# STBlitter_RevC2.net
KiCad netlist of a schematic drawn in EAGLE
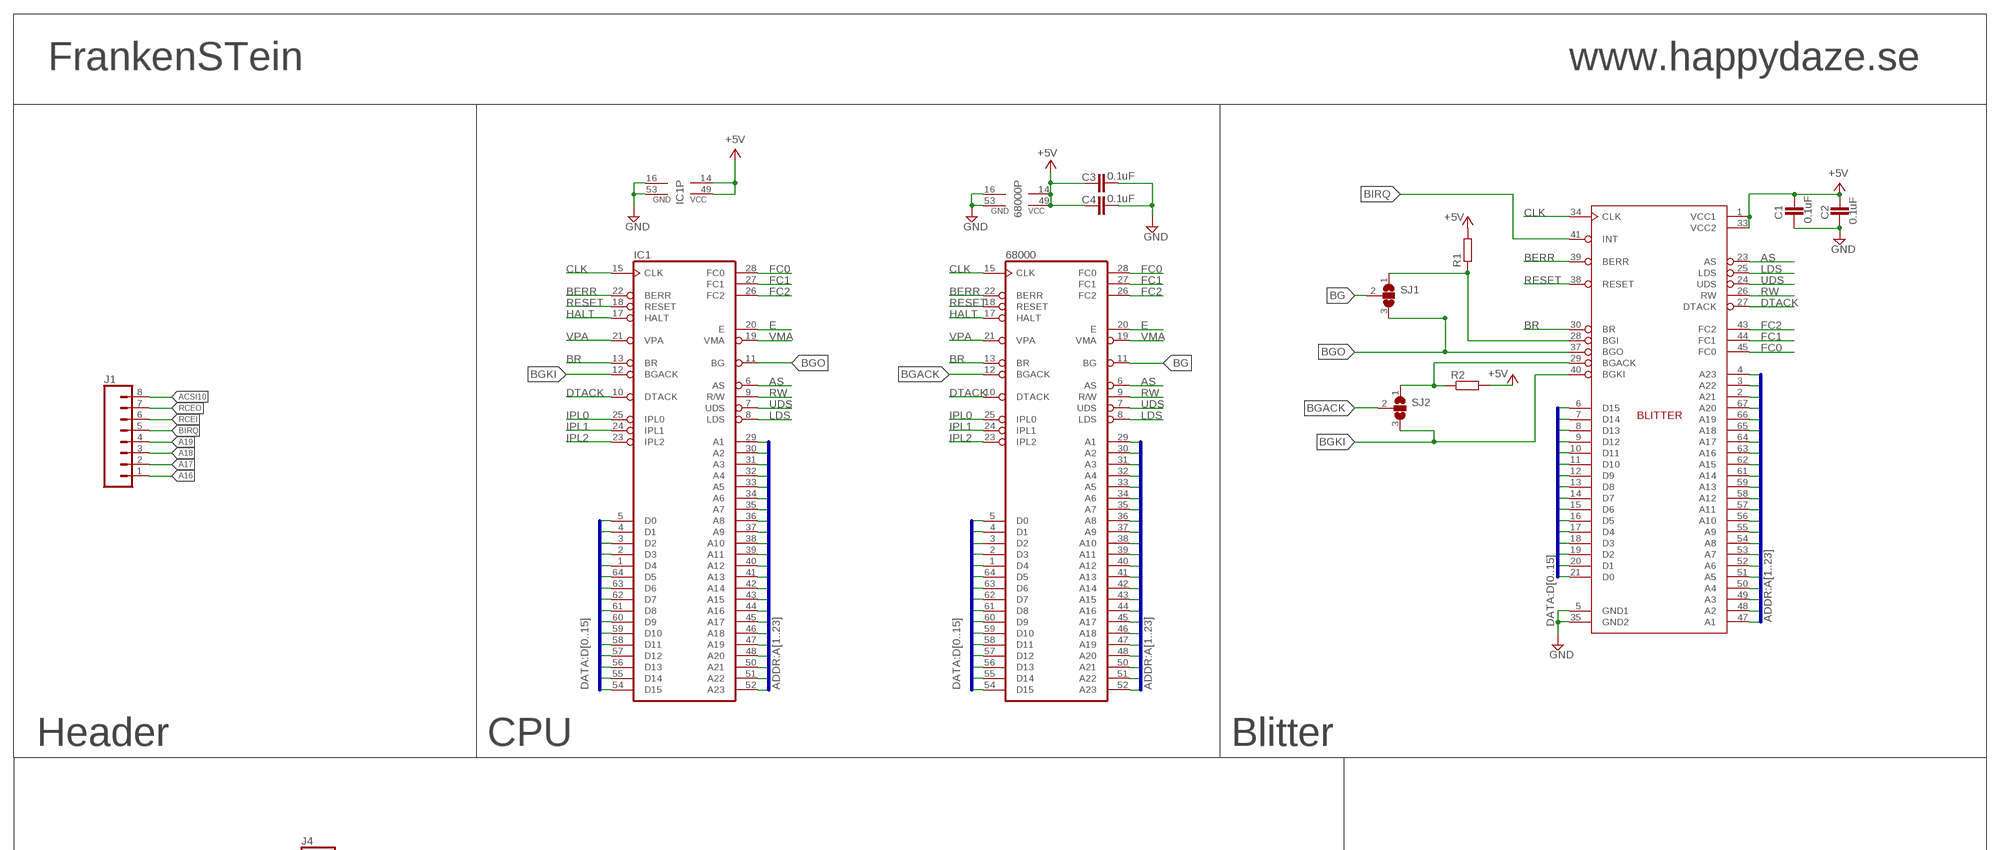
[diagram p0: schematic, sheet 1, part 1 of 2]
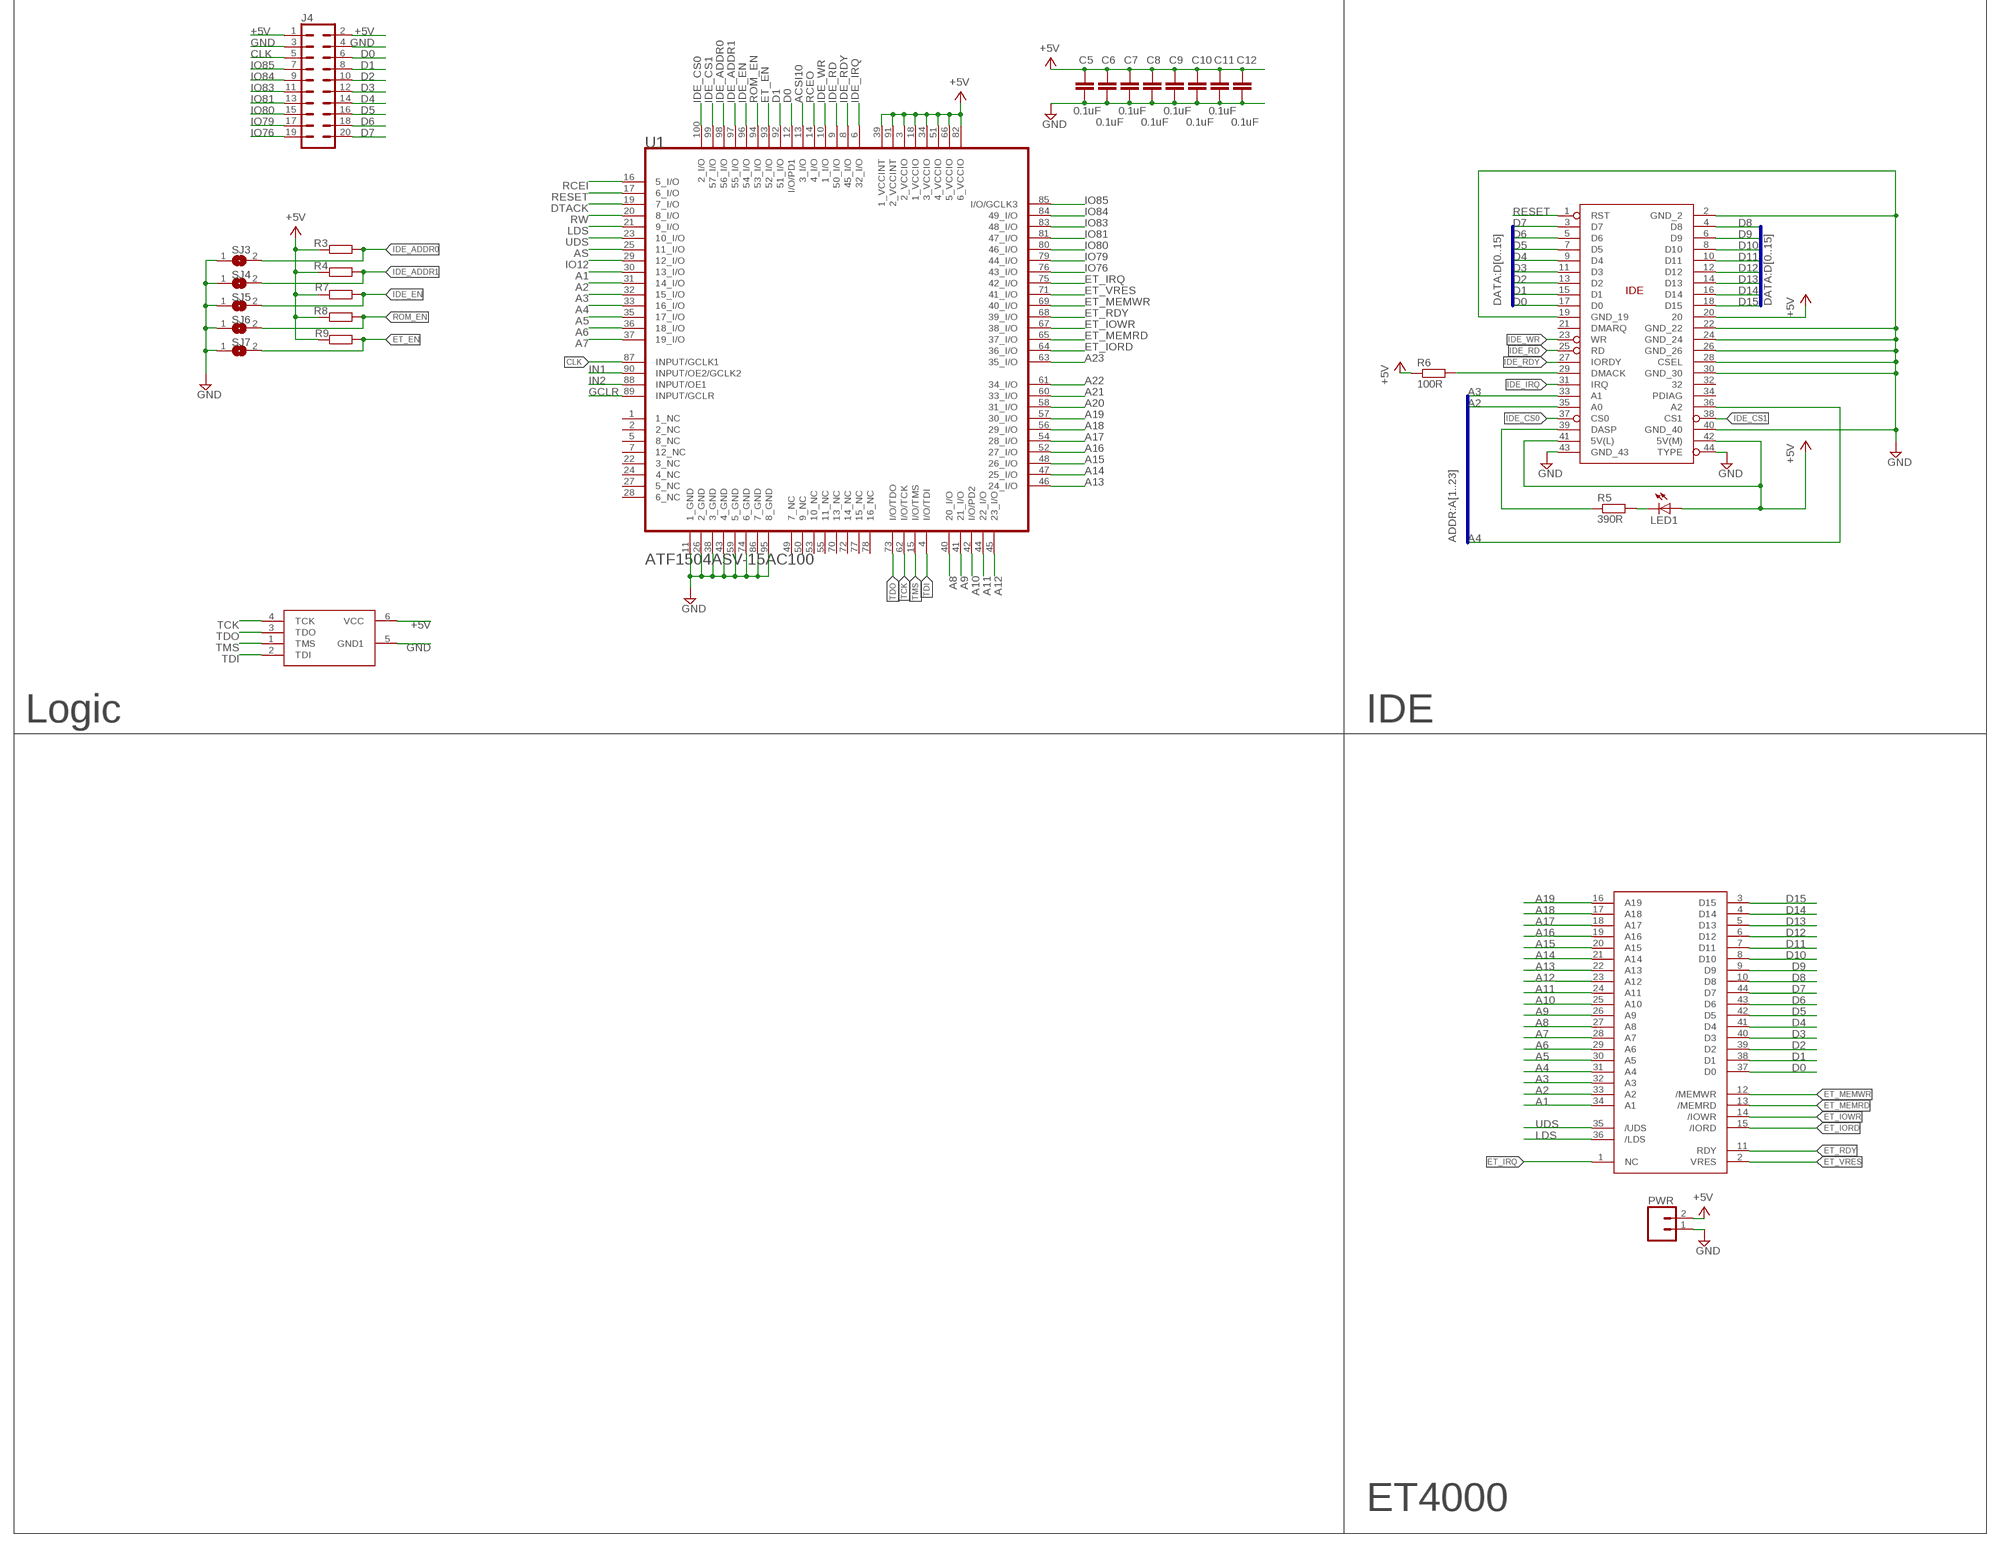
[diagram p1: schematic, sheet 1, part 2 of 2]

(export (version "E")
  (design (tool "Eeschema 10.0.6"))
  (components
    (comp (ref "68000")
      (value "MC68000P")
      (footprint "eagle-import:DIL64")
      (libsource (lib "eagle-import") (part "MC68000P"))
    )
    (comp (ref "BLITTER")
      (value "STBLITTER")
      (footprint "eagle-import:PLCC68-S")
      (libsource (lib "eagle-import") (part "STBLITTER"))
    )
    (comp (ref "C1")
      (value "0.1uF")
      (footprint "eagle-import:C0805")
      (libsource (lib "eagle-import") (part "C-EUC0805"))
    )
    (comp (ref "C2")
      (value "0.1uF")
      (footprint "eagle-import:C0805")
      (libsource (lib "eagle-import") (part "C-EUC0805"))
    )
    (comp (ref "C3")
      (value "0.1uF")
      (footprint "eagle-import:C0805")
      (libsource (lib "eagle-import") (part "C-EUC0805"))
    )
    (comp (ref "C4")
      (value "0.1uF")
      (footprint "eagle-import:C0805")
      (libsource (lib "eagle-import") (part "C-EUC0805"))
    )
    (comp (ref "C5")
      (value "0.1uF")
      (footprint "eagle-import:C0805")
      (libsource (lib "eagle-import") (part "C-EUC0805"))
    )
    (comp (ref "C6")
      (value "0.1uF")
      (footprint "eagle-import:C0805")
      (libsource (lib "eagle-import") (part "C-EUC0805"))
    )
    (comp (ref "C7")
      (value "0.1uF")
      (footprint "eagle-import:C0805")
      (libsource (lib "eagle-import") (part "C-EUC0805"))
    )
    (comp (ref "C8")
      (value "0.1uF")
      (footprint "eagle-import:C0805")
      (libsource (lib "eagle-import") (part "C-EUC0805"))
    )
    (comp (ref "C9")
      (value "0.1uF")
      (footprint "eagle-import:C0805")
      (libsource (lib "eagle-import") (part "C-EUC0805"))
    )
    (comp (ref "C10")
      (value "0.1uF")
      (footprint "eagle-import:C0805")
      (libsource (lib "eagle-import") (part "C-EUC0805"))
    )
    (comp (ref "C11")
      (value "0.1uF")
      (footprint "eagle-import:C0805")
      (libsource (lib "eagle-import") (part "C-EUC0805"))
    )
    (comp (ref "C12")
      (value "0.1uF")
      (footprint "eagle-import:C0805")
      (libsource (lib "eagle-import") (part "C-EUC0805"))
    )
    (comp (ref "CFCARD")
      (value "IDE44_CON")
      (footprint "eagle-import:IDE44_CON")
      (libsource (lib "eagle-import") (part "IDE44_CON"))
    )
    (comp (ref "IC1")
      (value "MC68000P2")
      (footprint "eagle-import:DIL64_SOCKET")
      (libsource (lib "eagle-import") (part "MC68000P2"))
    )
    (comp (ref "J1")
      (value "CONN_08\"")
      (footprint "eagle-import:1X08")
      (libsource (lib "eagle-import") (part "CONN_08{dblquote}"))
    )
    (comp (ref "J4")
      (value "CONN_10X2")
      (footprint "eagle-import:2X10")
      (libsource (lib "eagle-import") (part "CONN_10X2"))
    )
    (comp (ref "JTAG")
      (value "JTAG_ATDH2")
      (footprint "eagle-import:JTAG_ATDH2")
      (libsource (lib "eagle-import") (part "JTAG_ATDH2"))
    )
    (comp (ref "LED1")
      (value "LED3MM")
      (footprint "eagle-import:LED3MM")
      (libsource (lib "eagle-import") (part "LED3MM"))
    )
    (comp (ref "PWR")
      (value "CONN_02")
      (footprint "eagle-import:1X02")
      (libsource (lib "eagle-import") (part "CONN_02"))
    )
    (comp (ref "R1")
      (value "R-EU_R0805")
      (footprint "eagle-import:R0805")
      (libsource (lib "eagle-import") (part "R-EU_R0805"))
    )
    (comp (ref "R2")
      (value "R-EU_R0805")
      (footprint "eagle-import:R0805")
      (libsource (lib "eagle-import") (part "R-EU_R0805"))
    )
    (comp (ref "R3")
      (value "R-EU_R0805")
      (footprint "eagle-import:R0805")
      (libsource (lib "eagle-import") (part "R-EU_R0805"))
    )
    (comp (ref "R4")
      (value "R-EU_R0805")
      (footprint "eagle-import:R0805")
      (libsource (lib "eagle-import") (part "R-EU_R0805"))
    )
    (comp (ref "R5")
      (value "390R")
      (footprint "eagle-import:R0805")
      (libsource (lib "eagle-import") (part "R-EU_R0805"))
    )
    (comp (ref "R6")
      (value "100R")
      (footprint "eagle-import:R0805")
      (libsource (lib "eagle-import") (part "R-EU_R0805"))
    )
    (comp (ref "R7")
      (value "R-EU_R0805")
      (footprint "eagle-import:R0805")
      (libsource (lib "eagle-import") (part "R-EU_R0805"))
    )
    (comp (ref "R8")
      (value "R-EU_R0805")
      (footprint "eagle-import:R0805")
      (libsource (lib "eagle-import") (part "R-EU_R0805"))
    )
    (comp (ref "R9")
      (value "R-EU_R0805")
      (footprint "eagle-import:R0805")
      (libsource (lib "eagle-import") (part "R-EU_R0805"))
    )
    (comp (ref "SJ1")
      (value "SJ2W")
      (footprint "eagle-import:SJ_2")
      (libsource (lib "eagle-import") (part "SJ2W"))
    )
    (comp (ref "SJ2")
      (value "SJ2W")
      (footprint "eagle-import:SJ_2")
      (libsource (lib "eagle-import") (part "SJ2W"))
    )
    (comp (ref "SJ3") (value "SJ") (footprint "eagle-import:SJ") (libsource (lib "eagle-import") (part "SJ")))
    (comp (ref "SJ4") (value "SJ") (footprint "eagle-import:SJ") (libsource (lib "eagle-import") (part "SJ")))
    (comp (ref "SJ5") (value "SJ") (footprint "eagle-import:SJ") (libsource (lib "eagle-import") (part "SJ")))
    (comp (ref "SJ6") (value "SJ") (footprint "eagle-import:SJ") (libsource (lib "eagle-import") (part "SJ")))
    (comp (ref "SJ7") (value "SJ") (footprint "eagle-import:SJ") (libsource (lib "eagle-import") (part "SJ")))
    (comp (ref "STGA")
      (value "STGA")
      (footprint "eagle-import:STGACON")
      (libsource (lib "eagle-import") (part "STGA"))
    )
    (comp (ref "U1")
      (value "ATF1504_SMD100MICROCHIP_-_ATMEL_ATF1504ASV-15AC100_0_1")
      (footprint "eagle-import:MICROCHIP_-_ATMEL_ATF1504ASV-15AC100_1")
      (fields (field (name "MF") "Microchip / Atmel") (field (name "MPN") "ATF1504ASV-15AC100"))
      (libsource (lib "eagle-import") (part "ATF1504_SMD100MICROCHIP_-_ATMEL_ATF1504ASV-15AC100_0_1"))
    )
  )
  (nets
    (net (code "40") (name "+5V") (class "Default")
      (node (ref "68000") (pin "14") (pinfunction "VCC_14") (pintype "power_in"))
      (node (ref "68000") (pin "49") (pinfunction "VCC_49") (pintype "power_in"))
      (node (ref "BLITTER") (pin "1") (pinfunction "VCC1_1") (pintype "power_in"))
      (node (ref "BLITTER") (pin "33") (pinfunction "VCC2_33") (pintype "power_in"))
      (node (ref "C1") (pin "1") (pinfunction "1_1") (pintype "passive"))
      (node (ref "C10") (pin "2") (pinfunction "2_2") (pintype "passive"))
      (node (ref "C11") (pin "2") (pinfunction "2_2") (pintype "passive"))
      (node (ref "C12") (pin "2") (pinfunction "2_2") (pintype "passive"))
      (node (ref "C2") (pin "1") (pinfunction "1_1") (pintype "passive"))
      (node (ref "C3") (pin "1") (pinfunction "1_1") (pintype "passive"))
      (node (ref "C4") (pin "1") (pinfunction "1_1") (pintype "passive"))
      (node (ref "C5") (pin "2") (pinfunction "2_2") (pintype "passive"))
      (node (ref "C6") (pin "2") (pinfunction "2_2") (pintype "passive"))
      (node (ref "C7") (pin "2") (pinfunction "2_2") (pintype "passive"))
      (node (ref "C8") (pin "2") (pinfunction "2_2") (pintype "passive"))
      (node (ref "C9") (pin "2") (pinfunction "2_2") (pintype "passive"))
      (node (ref "CFCARD") (pin "20") (pinfunction "20_20") (pintype "bidirectional"))
      (node (ref "CFCARD") (pin "41") (pinfunction "5V(L)_41") (pintype "bidirectional"))
      (node (ref "CFCARD") (pin "42") (pinfunction "5V(M)_42") (pintype "bidirectional"))
      (node (ref "IC1") (pin "14") (pinfunction "VCC_14") (pintype "power_in"))
      (node (ref "IC1") (pin "49") (pinfunction "VCC_49") (pintype "power_in"))
      (node (ref "J4") (pin "1") (pinfunction "1_1") (pintype "passive"))
      (node (ref "J4") (pin "2") (pinfunction "2_2") (pintype "passive"))
      (node (ref "JTAG") (pin "6") (pinfunction "VCC_6") (pintype "bidirectional"))
      (node (ref "LED1") (pin "A") (pinfunction "A_A") (pintype "passive"))
      (node (ref "PWR") (pin "2") (pinfunction "2_2") (pintype "passive"))
      (node (ref "R1") (pin "2") (pinfunction "2_2") (pintype "passive"))
      (node (ref "R2") (pin "2") (pinfunction "2_2") (pintype "passive"))
      (node (ref "R3") (pin "1") (pinfunction "1_1") (pintype "passive"))
      (node (ref "R4") (pin "1") (pinfunction "1_1") (pintype "passive"))
      (node (ref "R6") (pin "1") (pinfunction "1_1") (pintype "passive"))
      (node (ref "R7") (pin "1") (pinfunction "1_1") (pintype "passive"))
      (node (ref "R8") (pin "1") (pinfunction "1_1") (pintype "passive"))
      (node (ref "R9") (pin "1") (pinfunction "1_1") (pintype "passive"))
      (node (ref "U1") (pin "18") (pinfunction "1_VCCIO_18") (pintype "power_in"))
      (node (ref "U1") (pin "3") (pinfunction "2_VCCIO_3") (pintype "power_in"))
      (node (ref "U1") (pin "34") (pinfunction "3_VCCIO_34") (pintype "power_in"))
      (node (ref "U1") (pin "39") (pinfunction "1_VCCINT_39") (pintype "power_in"))
      (node (ref "U1") (pin "51") (pinfunction "4_VCCIO_51") (pintype "power_in"))
      (node (ref "U1") (pin "66") (pinfunction "5_VCCIO_66") (pintype "power_in"))
      (node (ref "U1") (pin "82") (pinfunction "6_VCCIO_82") (pintype "power_in"))
      (node (ref "U1") (pin "91") (pinfunction "2_VCCINT_91") (pintype "power_in"))
    )
    (net (code "41") (name "/A1") (class "Default")
      (node (ref "68000") (pin "29") (pinfunction "A1_29") (pintype "output"))
      (node (ref "BLITTER") (pin "47") (pinfunction "A1_47") (pintype "bidirectional"))
      (node (ref "IC1") (pin "29") (pinfunction "A1_29") (pintype "output"))
      (node (ref "STGA") (pin "34") (pinfunction "A1_34") (pintype "bidirectional"))
      (node (ref "U1") (pin "30") (pinfunction "13_I/O_30") (pintype "bidirectional"))
    )
    (net (code "42") (name "/A2") (class "Default")
      (node (ref "68000") (pin "30") (pinfunction "A2_30") (pintype "output"))
      (node (ref "BLITTER") (pin "48") (pinfunction "A2_48") (pintype "bidirectional"))
      (node (ref "CFCARD") (pin "35") (pinfunction "A0_35") (pintype "bidirectional"))
      (node (ref "IC1") (pin "30") (pinfunction "A2_30") (pintype "output"))
      (node (ref "STGA") (pin "33") (pinfunction "A2_33") (pintype "bidirectional"))
      (node (ref "U1") (pin "31") (pinfunction "14_I/O_31") (pintype "bidirectional"))
    )
    (net (code "43") (name "/A3") (class "Default")
      (node (ref "68000") (pin "31") (pinfunction "A3_31") (pintype "output"))
      (node (ref "BLITTER") (pin "49") (pinfunction "A3_49") (pintype "bidirectional"))
      (node (ref "CFCARD") (pin "33") (pinfunction "A1_33") (pintype "bidirectional"))
      (node (ref "IC1") (pin "31") (pinfunction "A3_31") (pintype "output"))
      (node (ref "STGA") (pin "32") (pinfunction "A3_32") (pintype "bidirectional"))
      (node (ref "U1") (pin "32") (pinfunction "15_I/O_32") (pintype "bidirectional"))
    )
    (net (code "44") (name "/A4") (class "Default")
      (node (ref "68000") (pin "32") (pinfunction "A4_32") (pintype "output"))
      (node (ref "BLITTER") (pin "50") (pinfunction "A4_50") (pintype "bidirectional"))
      (node (ref "CFCARD") (pin "36") (pinfunction "A2_36") (pintype "bidirectional"))
      (node (ref "IC1") (pin "32") (pinfunction "A4_32") (pintype "output"))
      (node (ref "STGA") (pin "31") (pinfunction "A4_31") (pintype "bidirectional"))
      (node (ref "U1") (pin "33") (pinfunction "16_I/O_33") (pintype "bidirectional"))
    )
    (net (code "45") (name "/A5") (class "Default")
      (node (ref "68000") (pin "33") (pinfunction "A5_33") (pintype "output"))
      (node (ref "BLITTER") (pin "51") (pinfunction "A5_51") (pintype "bidirectional"))
      (node (ref "IC1") (pin "33") (pinfunction "A5_33") (pintype "output"))
      (node (ref "STGA") (pin "30") (pinfunction "A5_30") (pintype "bidirectional"))
      (node (ref "U1") (pin "35") (pinfunction "17_I/O_35") (pintype "bidirectional"))
    )
    (net (code "46") (name "/A6") (class "Default")
      (node (ref "68000") (pin "34") (pinfunction "A6_34") (pintype "output"))
      (node (ref "BLITTER") (pin "52") (pinfunction "A6_52") (pintype "bidirectional"))
      (node (ref "IC1") (pin "34") (pinfunction "A6_34") (pintype "output"))
      (node (ref "STGA") (pin "29") (pinfunction "A6_29") (pintype "bidirectional"))
      (node (ref "U1") (pin "36") (pinfunction "18_I/O_36") (pintype "bidirectional"))
    )
    (net (code "47") (name "/A7") (class "Default")
      (node (ref "68000") (pin "35") (pinfunction "A7_35") (pintype "output"))
      (node (ref "BLITTER") (pin "53") (pinfunction "A7_53") (pintype "bidirectional"))
      (node (ref "IC1") (pin "35") (pinfunction "A7_35") (pintype "output"))
      (node (ref "STGA") (pin "28") (pinfunction "A7_28") (pintype "bidirectional"))
      (node (ref "U1") (pin "37") (pinfunction "19_I/O_37") (pintype "bidirectional"))
    )
    (net (code "48") (name "/A8") (class "Default")
      (node (ref "68000") (pin "36") (pinfunction "A8_36") (pintype "output"))
      (node (ref "BLITTER") (pin "54") (pinfunction "A8_54") (pintype "bidirectional"))
      (node (ref "IC1") (pin "36") (pinfunction "A8_36") (pintype "output"))
      (node (ref "STGA") (pin "27") (pinfunction "A8_27") (pintype "bidirectional"))
      (node (ref "U1") (pin "40") (pinfunction "20_I/O_40") (pintype "bidirectional"))
    )
    (net (code "49") (name "/A9") (class "Default")
      (node (ref "68000") (pin "37") (pinfunction "A9_37") (pintype "output"))
      (node (ref "BLITTER") (pin "55") (pinfunction "A9_55") (pintype "bidirectional"))
      (node (ref "IC1") (pin "37") (pinfunction "A9_37") (pintype "output"))
      (node (ref "STGA") (pin "26") (pinfunction "A9_26") (pintype "bidirectional"))
      (node (ref "U1") (pin "41") (pinfunction "21_I/O_41") (pintype "bidirectional"))
    )
    (net (code "50") (name "/A10") (class "Default")
      (node (ref "68000") (pin "38") (pinfunction "A10_38") (pintype "output"))
      (node (ref "BLITTER") (pin "56") (pinfunction "A10_56") (pintype "bidirectional"))
      (node (ref "IC1") (pin "38") (pinfunction "A10_38") (pintype "output"))
      (node (ref "STGA") (pin "25") (pinfunction "A10_25") (pintype "bidirectional"))
      (node (ref "U1") (pin "42") (pinfunction "I/O/PD2_42") (pintype "bidirectional"))
    )
    (net (code "51") (name "/A11") (class "Default")
      (node (ref "68000") (pin "39") (pinfunction "A11_39") (pintype "output"))
      (node (ref "BLITTER") (pin "57") (pinfunction "A11_57") (pintype "bidirectional"))
      (node (ref "IC1") (pin "39") (pinfunction "A11_39") (pintype "output"))
      (node (ref "STGA") (pin "24") (pinfunction "A11_24") (pintype "bidirectional"))
      (node (ref "U1") (pin "44") (pinfunction "22_I/O_44") (pintype "bidirectional"))
    )
    (net (code "52") (name "/A12") (class "Default")
      (node (ref "68000") (pin "40") (pinfunction "A12_40") (pintype "output"))
      (node (ref "BLITTER") (pin "58") (pinfunction "A12_58") (pintype "bidirectional"))
      (node (ref "IC1") (pin "40") (pinfunction "A12_40") (pintype "output"))
      (node (ref "STGA") (pin "23") (pinfunction "A12_23") (pintype "bidirectional"))
      (node (ref "U1") (pin "45") (pinfunction "23_I/O_45") (pintype "bidirectional"))
    )
    (net (code "53") (name "/A13") (class "Default")
      (node (ref "68000") (pin "41") (pinfunction "A13_41") (pintype "output"))
      (node (ref "BLITTER") (pin "59") (pinfunction "A13_59") (pintype "bidirectional"))
      (node (ref "IC1") (pin "41") (pinfunction "A13_41") (pintype "output"))
      (node (ref "STGA") (pin "22") (pinfunction "A13_22") (pintype "bidirectional"))
      (node (ref "U1") (pin "46") (pinfunction "24_I/O_46") (pintype "bidirectional"))
    )
    (net (code "54") (name "/A14") (class "Default")
      (node (ref "68000") (pin "42") (pinfunction "A14_42") (pintype "output"))
      (node (ref "BLITTER") (pin "61") (pinfunction "A14_61") (pintype "bidirectional"))
      (node (ref "IC1") (pin "42") (pinfunction "A14_42") (pintype "output"))
      (node (ref "STGA") (pin "21") (pinfunction "A14_21") (pintype "bidirectional"))
      (node (ref "U1") (pin "47") (pinfunction "25_I/O_47") (pintype "bidirectional"))
    )
    (net (code "55") (name "/A15") (class "Default")
      (node (ref "68000") (pin "43") (pinfunction "A15_43") (pintype "output"))
      (node (ref "BLITTER") (pin "62") (pinfunction "A15_62") (pintype "bidirectional"))
      (node (ref "IC1") (pin "43") (pinfunction "A15_43") (pintype "output"))
      (node (ref "STGA") (pin "20") (pinfunction "A15_20") (pintype "bidirectional"))
      (node (ref "U1") (pin "48") (pinfunction "26_I/O_48") (pintype "bidirectional"))
    )
    (net (code "56") (name "/A20") (class "Default")
      (node (ref "68000") (pin "48") (pinfunction "A20_48") (pintype "output"))
      (node (ref "BLITTER") (pin "67") (pinfunction "A20_67") (pintype "bidirectional"))
      (node (ref "IC1") (pin "48") (pinfunction "A20_48") (pintype "output"))
      (node (ref "U1") (pin "58") (pinfunction "31_I/O_58") (pintype "bidirectional"))
    )
    (net (code "57") (name "/A21") (class "Default")
      (node (ref "68000") (pin "50") (pinfunction "A21_50") (pintype "output"))
      (node (ref "BLITTER") (pin "2") (pinfunction "A21_2") (pintype "bidirectional"))
      (node (ref "IC1") (pin "50") (pinfunction "A21_50") (pintype "output"))
      (node (ref "U1") (pin "60") (pinfunction "33_I/O_60") (pintype "bidirectional"))
    )
    (net (code "58") (name "/A22") (class "Default")
      (node (ref "68000") (pin "51") (pinfunction "A22_51") (pintype "output"))
      (node (ref "BLITTER") (pin "3") (pinfunction "A22_3") (pintype "bidirectional"))
      (node (ref "IC1") (pin "51") (pinfunction "A22_51") (pintype "output"))
      (node (ref "U1") (pin "61") (pinfunction "34_I/O_61") (pintype "bidirectional"))
    )
    (net (code "59") (name "/A23") (class "Default")
      (node (ref "68000") (pin "52") (pinfunction "A23_52") (pintype "output"))
      (node (ref "BLITTER") (pin "4") (pinfunction "A23_4") (pintype "bidirectional"))
      (node (ref "IC1") (pin "52") (pinfunction "A23_52") (pintype "output"))
      (node (ref "U1") (pin "63") (pinfunction "35_I/O_63") (pintype "bidirectional"))
    )
    (net (code "61") (name "/AS") (class "Default")
      (node (ref "68000") (pin "6") (pinfunction "AS_6") (pintype "output"))
      (node (ref "BLITTER") (pin "23") (pinfunction "AS_23") (pintype "bidirectional"))
      (node (ref "IC1") (pin "6") (pinfunction "AS_6") (pintype "output"))
      (node (ref "U1") (pin "25") (pinfunction "11_I/O_25") (pintype "bidirectional"))
    )
    (net (code "62") (name "/BERR") (class "Default")
      (node (ref "68000") (pin "22") (pinfunction "BERR_22") (pintype "input"))
      (node (ref "BLITTER") (pin "39") (pinfunction "BERR_39") (pintype "bidirectional"))
      (node (ref "IC1") (pin "22") (pinfunction "BERR_22") (pintype "input"))
    )
    (net (code "63") (name "/BR") (class "Default")
      (node (ref "68000") (pin "13") (pinfunction "BR_13") (pintype "input"))
      (node (ref "BLITTER") (pin "30") (pinfunction "BR_30") (pintype "bidirectional"))
      (node (ref "IC1") (pin "13") (pinfunction "BR_13") (pintype "input"))
    )
    (net (code "64") (name "/D0") (class "Default")
      (node (ref "68000") (pin "5") (pinfunction "D0_5") (pintype "bidirectional"))
      (node (ref "BLITTER") (pin "21") (pinfunction "D0_21") (pintype "bidirectional"))
      (node (ref "CFCARD") (pin "17") (pinfunction "D0_17") (pintype "bidirectional"))
      (node (ref "IC1") (pin "5") (pinfunction "D0_5") (pintype "bidirectional"))
      (node (ref "J4") (pin "6") (pinfunction "6_6") (pintype "passive"))
      (node (ref "STGA") (pin "37") (pinfunction "D0_37") (pintype "bidirectional"))
      (node (ref "U1") (pin "12") (pinfunction "I/O/PD1_12") (pintype "bidirectional"))
    )
    (net (code "65") (name "/D1") (class "Default")
      (node (ref "68000") (pin "4") (pinfunction "D1_4") (pintype "bidirectional"))
      (node (ref "BLITTER") (pin "20") (pinfunction "D1_20") (pintype "bidirectional"))
      (node (ref "CFCARD") (pin "15") (pinfunction "D1_15") (pintype "bidirectional"))
      (node (ref "IC1") (pin "4") (pinfunction "D1_4") (pintype "bidirectional"))
      (node (ref "J4") (pin "8") (pinfunction "8_8") (pintype "passive"))
      (node (ref "STGA") (pin "38") (pinfunction "D1_38") (pintype "bidirectional"))
      (node (ref "U1") (pin "92") (pinfunction "51_I/O_92") (pintype "bidirectional"))
    )
    (net (code "66") (name "/D2") (class "Default")
      (node (ref "68000") (pin "3") (pinfunction "D2_3") (pintype "bidirectional"))
      (node (ref "BLITTER") (pin "19") (pinfunction "D2_19") (pintype "bidirectional"))
      (node (ref "CFCARD") (pin "13") (pinfunction "D2_13") (pintype "bidirectional"))
      (node (ref "IC1") (pin "3") (pinfunction "D2_3") (pintype "bidirectional"))
      (node (ref "J4") (pin "10") (pinfunction "10_10") (pintype "passive"))
      (node (ref "STGA") (pin "39") (pinfunction "D2_39") (pintype "bidirectional"))
    )
    (net (code "67") (name "/D3") (class "Default")
      (node (ref "68000") (pin "2") (pinfunction "D3_2") (pintype "bidirectional"))
      (node (ref "BLITTER") (pin "18") (pinfunction "D3_18") (pintype "bidirectional"))
      (node (ref "CFCARD") (pin "11") (pinfunction "D3_11") (pintype "bidirectional"))
      (node (ref "IC1") (pin "2") (pinfunction "D3_2") (pintype "bidirectional"))
      (node (ref "J4") (pin "12") (pinfunction "12_12") (pintype "passive"))
      (node (ref "STGA") (pin "40") (pinfunction "D3_40") (pintype "bidirectional"))
    )
    (net (code "68") (name "/D4") (class "Default")
      (node (ref "68000") (pin "1") (pinfunction "D4_1") (pintype "bidirectional"))
      (node (ref "BLITTER") (pin "17") (pinfunction "D4_17") (pintype "bidirectional"))
      (node (ref "CFCARD") (pin "9") (pinfunction "D4_9") (pintype "bidirectional"))
      (node (ref "IC1") (pin "1") (pinfunction "D4_1") (pintype "bidirectional"))
      (node (ref "J4") (pin "14") (pinfunction "14_14") (pintype "passive"))
      (node (ref "STGA") (pin "41") (pinfunction "D4_41") (pintype "bidirectional"))
    )
    (net (code "69") (name "/D5") (class "Default")
      (node (ref "68000") (pin "64") (pinfunction "D5_64") (pintype "bidirectional"))
      (node (ref "BLITTER") (pin "16") (pinfunction "D5_16") (pintype "bidirectional"))
      (node (ref "CFCARD") (pin "7") (pinfunction "D5_7") (pintype "bidirectional"))
      (node (ref "IC1") (pin "64") (pinfunction "D5_64") (pintype "bidirectional"))
      (node (ref "J4") (pin "16") (pinfunction "16_16") (pintype "passive"))
      (node (ref "STGA") (pin "42") (pinfunction "D5_42") (pintype "bidirectional"))
    )
    (net (code "70") (name "/D6") (class "Default")
      (node (ref "68000") (pin "63") (pinfunction "D6_63") (pintype "bidirectional"))
      (node (ref "BLITTER") (pin "15") (pinfunction "D6_15") (pintype "bidirectional"))
      (node (ref "CFCARD") (pin "5") (pinfunction "D6_5") (pintype "bidirectional"))
      (node (ref "IC1") (pin "63") (pinfunction "D6_63") (pintype "bidirectional"))
      (node (ref "J4") (pin "18") (pinfunction "18_18") (pintype "passive"))
      (node (ref "STGA") (pin "43") (pinfunction "D6_43") (pintype "bidirectional"))
    )
    (net (code "71") (name "/D7") (class "Default")
      (node (ref "68000") (pin "62") (pinfunction "D7_62") (pintype "bidirectional"))
      (node (ref "BLITTER") (pin "14") (pinfunction "D7_14") (pintype "bidirectional"))
      (node (ref "CFCARD") (pin "3") (pinfunction "D7_3") (pintype "bidirectional"))
      (node (ref "IC1") (pin "62") (pinfunction "D7_62") (pintype "bidirectional"))
      (node (ref "J4") (pin "20") (pinfunction "20_20") (pintype "passive"))
      (node (ref "STGA") (pin "44") (pinfunction "D7_44") (pintype "bidirectional"))
    )
    (net (code "72") (name "/D8") (class "Default")
      (node (ref "68000") (pin "61") (pinfunction "D8_61") (pintype "bidirectional"))
      (node (ref "BLITTER") (pin "13") (pinfunction "D8_13") (pintype "bidirectional"))
      (node (ref "CFCARD") (pin "4") (pinfunction "D8_4") (pintype "bidirectional"))
      (node (ref "IC1") (pin "61") (pinfunction "D8_61") (pintype "bidirectional"))
      (node (ref "STGA") (pin "10") (pinfunction "D8_10") (pintype "bidirectional"))
    )
    (net (code "73") (name "/D9") (class "Default")
      (node (ref "68000") (pin "60") (pinfunction "D9_60") (pintype "bidirectional"))
      (node (ref "BLITTER") (pin "12") (pinfunction "D9_12") (pintype "bidirectional"))
      (node (ref "CFCARD") (pin "6") (pinfunction "D9_6") (pintype "bidirectional"))
      (node (ref "IC1") (pin "60") (pinfunction "D9_60") (pintype "bidirectional"))
      (node (ref "STGA") (pin "9") (pinfunction "D9_9") (pintype "bidirectional"))
    )
    (net (code "74") (name "/D10") (class "Default")
      (node (ref "68000") (pin "59") (pinfunction "D10_59") (pintype "bidirectional"))
      (node (ref "BLITTER") (pin "11") (pinfunction "D10_11") (pintype "bidirectional"))
      (node (ref "CFCARD") (pin "8") (pinfunction "D10_8") (pintype "bidirectional"))
      (node (ref "IC1") (pin "59") (pinfunction "D10_59") (pintype "bidirectional"))
      (node (ref "STGA") (pin "8") (pinfunction "D10_8") (pintype "bidirectional"))
    )
    (net (code "75") (name "/D11") (class "Default")
      (node (ref "68000") (pin "58") (pinfunction "D11_58") (pintype "bidirectional"))
      (node (ref "BLITTER") (pin "10") (pinfunction "D11_10") (pintype "bidirectional"))
      (node (ref "CFCARD") (pin "10") (pinfunction "D11_10") (pintype "bidirectional"))
      (node (ref "IC1") (pin "58") (pinfunction "D11_58") (pintype "bidirectional"))
      (node (ref "STGA") (pin "7") (pinfunction "D11_7") (pintype "bidirectional"))
    )
    (net (code "76") (name "/D12") (class "Default")
      (node (ref "68000") (pin "57") (pinfunction "D12_57") (pintype "bidirectional"))
      (node (ref "BLITTER") (pin "9") (pinfunction "D12_9") (pintype "bidirectional"))
      (node (ref "CFCARD") (pin "12") (pinfunction "D12_12") (pintype "bidirectional"))
      (node (ref "IC1") (pin "57") (pinfunction "D12_57") (pintype "bidirectional"))
      (node (ref "STGA") (pin "6") (pinfunction "D12_6") (pintype "bidirectional"))
    )
    (net (code "77") (name "/D13") (class "Default")
      (node (ref "68000") (pin "56") (pinfunction "D13_56") (pintype "bidirectional"))
      (node (ref "BLITTER") (pin "8") (pinfunction "D13_8") (pintype "bidirectional"))
      (node (ref "CFCARD") (pin "14") (pinfunction "D13_14") (pintype "bidirectional"))
      (node (ref "IC1") (pin "56") (pinfunction "D13_56") (pintype "bidirectional"))
      (node (ref "STGA") (pin "5") (pinfunction "D13_5") (pintype "bidirectional"))
    )
    (net (code "78") (name "/D14") (class "Default")
      (node (ref "68000") (pin "55") (pinfunction "D14_55") (pintype "bidirectional"))
      (node (ref "BLITTER") (pin "7") (pinfunction "D14_7") (pintype "bidirectional"))
      (node (ref "CFCARD") (pin "16") (pinfunction "D14_16") (pintype "bidirectional"))
      (node (ref "IC1") (pin "55") (pinfunction "D14_55") (pintype "bidirectional"))
      (node (ref "STGA") (pin "4") (pinfunction "D14_4") (pintype "bidirectional"))
    )
    (net (code "79") (name "/D15") (class "Default")
      (node (ref "68000") (pin "54") (pinfunction "D15_54") (pintype "bidirectional"))
      (node (ref "BLITTER") (pin "6") (pinfunction "D15_6") (pintype "bidirectional"))
      (node (ref "CFCARD") (pin "18") (pinfunction "D15_18") (pintype "bidirectional"))
      (node (ref "IC1") (pin "54") (pinfunction "D15_54") (pintype "bidirectional"))
      (node (ref "STGA") (pin "3") (pinfunction "D15_3") (pintype "bidirectional"))
    )
    (net (code "81") (name "/DTACK") (class "Default")
      (node (ref "68000") (pin "10") (pinfunction "DTACK_10") (pintype "input"))
      (node (ref "BLITTER") (pin "27") (pinfunction "DTACK_27") (pintype "bidirectional"))
      (node (ref "IC1") (pin "10") (pinfunction "DTACK_10") (pintype "input"))
      (node (ref "U1") (pin "19") (pinfunction "7_I/O_19") (pintype "bidirectional"))
    )
    (net (code "82") (name "/E") (class "Default")
      (node (ref "68000") (pin "20") (pinfunction "E_20") (pintype "output"))
      (node (ref "IC1") (pin "20") (pinfunction "E_20") (pintype "output"))
    )
    (net (code "83") (name "/FC0") (class "Default")
      (node (ref "68000") (pin "28") (pinfunction "FC0_28") (pintype "output"))
      (node (ref "BLITTER") (pin "45") (pinfunction "FC0_45") (pintype "bidirectional"))
      (node (ref "IC1") (pin "28") (pinfunction "FC0_28") (pintype "output"))
    )
    (net (code "84") (name "/FC1") (class "Default")
      (node (ref "68000") (pin "27") (pinfunction "FC1_27") (pintype "output"))
      (node (ref "BLITTER") (pin "44") (pinfunction "FC1_44") (pintype "bidirectional"))
      (node (ref "IC1") (pin "27") (pinfunction "FC1_27") (pintype "output"))
    )
    (net (code "85") (name "/FC2") (class "Default")
      (node (ref "68000") (pin "26") (pinfunction "FC2_26") (pintype "output"))
      (node (ref "BLITTER") (pin "43") (pinfunction "FC2_43") (pintype "bidirectional"))
      (node (ref "IC1") (pin "26") (pinfunction "FC2_26") (pintype "output"))
    )
    (net (code "86") (name "/GCLR") (class "Default")
      (node (ref "U1") (pin "89") (pinfunction "INPUT/GCLR_89") (pintype "input"))
    )
    (net (code "87") (name "/HALT") (class "Default")
      (node (ref "68000") (pin "17") (pinfunction "HALT_17") (pintype "bidirectional"))
      (node (ref "IC1") (pin "17") (pinfunction "HALT_17") (pintype "bidirectional"))
    )
    (net (code "88") (name "/IN1") (class "Default")
      (node (ref "U1") (pin "90") (pinfunction "INPUT/OE2/GCLK2_90") (pintype "input"))
    )
    (net (code "89") (name "/IN2") (class "Default")
      (node (ref "U1") (pin "88") (pinfunction "INPUT/OE1_88") (pintype "input"))
    )
    (net (code "90") (name "/IO12") (class "Default")
      (node (ref "U1") (pin "29") (pinfunction "12_I/O_29") (pintype "bidirectional"))
    )
    (net (code "91") (name "/IO76") (class "Default")
      (node (ref "J4") (pin "19") (pinfunction "19_19") (pintype "passive"))
      (node (ref "U1") (pin "76") (pinfunction "43_I/O_76") (pintype "bidirectional"))
    )
    (net (code "92") (name "/IO79") (class "Default")
      (node (ref "J4") (pin "17") (pinfunction "17_17") (pintype "passive"))
      (node (ref "U1") (pin "79") (pinfunction "44_I/O_79") (pintype "bidirectional"))
    )
    (net (code "93") (name "/IO80") (class "Default")
      (node (ref "J4") (pin "15") (pinfunction "15_15") (pintype "passive"))
      (node (ref "U1") (pin "80") (pinfunction "46_I/O_80") (pintype "bidirectional"))
    )
    (net (code "94") (name "/IO81") (class "Default")
      (node (ref "J4") (pin "13") (pinfunction "13_13") (pintype "passive"))
      (node (ref "U1") (pin "81") (pinfunction "47_I/O_81") (pintype "bidirectional"))
    )
    (net (code "95") (name "/IO83") (class "Default")
      (node (ref "J4") (pin "11") (pinfunction "11_11") (pintype "passive"))
      (node (ref "U1") (pin "83") (pinfunction "48_I/O_83") (pintype "bidirectional"))
    )
    (net (code "96") (name "/IO84") (class "Default")
      (node (ref "J4") (pin "9") (pinfunction "9_9") (pintype "passive"))
      (node (ref "U1") (pin "84") (pinfunction "49_I/O_84") (pintype "bidirectional"))
    )
    (net (code "97") (name "/IO85") (class "Default")
      (node (ref "J4") (pin "7") (pinfunction "7_7") (pintype "passive"))
      (node (ref "U1") (pin "85") (pinfunction "I/O/GCLK3_85") (pintype "bidirectional"))
    )
    (net (code "98") (name "/IPL0") (class "Default")
      (node (ref "68000") (pin "25") (pinfunction "IPL0_25") (pintype "input"))
      (node (ref "IC1") (pin "25") (pinfunction "IPL0_25") (pintype "input"))
    )
    (net (code "99") (name "/IPL1") (class "Default")
      (node (ref "68000") (pin "24") (pinfunction "IPL1_24") (pintype "input"))
      (node (ref "IC1") (pin "24") (pinfunction "IPL1_24") (pintype "input"))
    )
    (net (code "100") (name "/IPL2") (class "Default")
      (node (ref "68000") (pin "23") (pinfunction "IPL2_23") (pintype "input"))
      (node (ref "IC1") (pin "23") (pinfunction "IPL2_23") (pintype "input"))
    )
    (net (code "101") (name "/LDS") (class "Default")
      (node (ref "68000") (pin "8") (pinfunction "LDS_8") (pintype "output"))
      (node (ref "BLITTER") (pin "25") (pinfunction "LDS_25") (pintype "bidirectional"))
      (node (ref "IC1") (pin "8") (pinfunction "LDS_8") (pintype "output"))
      (node (ref "STGA") (pin "36") (pinfunction "/LDS_36") (pintype "bidirectional"))
      (node (ref "U1") (pin "21") (pinfunction "9_I/O_21") (pintype "bidirectional"))
    )
    (net (code "102") (name "/RESET") (class "Default")
      (node (ref "68000") (pin "18") (pinfunction "RESET_18") (pintype "bidirectional"))
      (node (ref "BLITTER") (pin "38") (pinfunction "RESET_38") (pintype "bidirectional"))
      (node (ref "CFCARD") (pin "1") (pinfunction "RST_1") (pintype "bidirectional"))
      (node (ref "IC1") (pin "18") (pinfunction "RESET_18") (pintype "bidirectional"))
      (node (ref "U1") (pin "17") (pinfunction "6_I/O_17") (pintype "bidirectional"))
    )
    (net (code "103") (name "/RW") (class "Default")
      (node (ref "68000") (pin "9") (pinfunction "R/W_9") (pintype "output"))
      (node (ref "BLITTER") (pin "26") (pinfunction "RW_26") (pintype "bidirectional"))
      (node (ref "IC1") (pin "9") (pinfunction "R/W_9") (pintype "output"))
      (node (ref "U1") (pin "20") (pinfunction "8_I/O_20") (pintype "bidirectional"))
    )
    (net (code "104") (name "/UDS") (class "Default")
      (node (ref "68000") (pin "7") (pinfunction "UDS_7") (pintype "output"))
      (node (ref "BLITTER") (pin "24") (pinfunction "UDS_24") (pintype "bidirectional"))
      (node (ref "IC1") (pin "7") (pinfunction "UDS_7") (pintype "output"))
      (node (ref "STGA") (pin "35") (pinfunction "/UDS_35") (pintype "bidirectional"))
      (node (ref "U1") (pin "23") (pinfunction "10_I/O_23") (pintype "bidirectional"))
    )
    (net (code "105") (name "/VMA") (class "Default")
      (node (ref "68000") (pin "19") (pinfunction "VMA_19") (pintype "output"))
      (node (ref "IC1") (pin "19") (pinfunction "VMA_19") (pintype "output"))
    )
    (net (code "106") (name "/VPA") (class "Default")
      (node (ref "68000") (pin "21") (pinfunction "VPA_21") (pintype "input"))
      (node (ref "IC1") (pin "21") (pinfunction "VPA_21") (pintype "input"))
    )
    (net (code "107") (name "A16") (class "Default")
      (node (ref "68000") (pin "44") (pinfunction "A16_44") (pintype "output"))
      (node (ref "BLITTER") (pin "63") (pinfunction "A16_63") (pintype "bidirectional"))
      (node (ref "IC1") (pin "44") (pinfunction "A16_44") (pintype "output"))
      (node (ref "J1") (pin "1") (pinfunction "1_1") (pintype "passive"))
      (node (ref "STGA") (pin "19") (pinfunction "A16_19") (pintype "bidirectional"))
      (node (ref "U1") (pin "52") (pinfunction "27_I/O_52") (pintype "bidirectional"))
    )
    (net (code "108") (name "A17") (class "Default")
      (node (ref "68000") (pin "45") (pinfunction "A17_45") (pintype "output"))
      (node (ref "BLITTER") (pin "64") (pinfunction "A17_64") (pintype "bidirectional"))
      (node (ref "IC1") (pin "45") (pinfunction "A17_45") (pintype "output"))
      (node (ref "J1") (pin "2") (pinfunction "2_2") (pintype "passive"))
      (node (ref "STGA") (pin "18") (pinfunction "A17_18") (pintype "bidirectional"))
      (node (ref "U1") (pin "54") (pinfunction "28_I/O_54") (pintype "bidirectional"))
    )
    (net (code "109") (name "A18") (class "Default")
      (node (ref "68000") (pin "46") (pinfunction "A18_46") (pintype "output"))
      (node (ref "BLITTER") (pin "65") (pinfunction "A18_65") (pintype "bidirectional"))
      (node (ref "IC1") (pin "46") (pinfunction "A18_46") (pintype "output"))
      (node (ref "J1") (pin "3") (pinfunction "3_3") (pintype "passive"))
      (node (ref "STGA") (pin "17") (pinfunction "A18_17") (pintype "bidirectional"))
      (node (ref "U1") (pin "56") (pinfunction "29_I/O_56") (pintype "bidirectional"))
    )
    (net (code "110") (name "A19") (class "Default")
      (node (ref "68000") (pin "47") (pinfunction "A19_47") (pintype "output"))
      (node (ref "BLITTER") (pin "66") (pinfunction "A19_66") (pintype "bidirectional"))
      (node (ref "IC1") (pin "47") (pinfunction "A19_47") (pintype "output"))
      (node (ref "J1") (pin "4") (pinfunction "4_4") (pintype "passive"))
      (node (ref "STGA") (pin "16") (pinfunction "A19_16") (pintype "bidirectional"))
      (node (ref "U1") (pin "57") (pinfunction "30_I/O_57") (pintype "bidirectional"))
    )
    (net (code "111") (name "ACSI10") (class "Default")
      (node (ref "J1") (pin "8") (pinfunction "8_8") (pintype "passive"))
      (node (ref "U1") (pin "13") (pinfunction "3_I/O_13") (pintype "bidirectional"))
    )
    (net (code "112") (name "BG") (class "Default")
      (node (ref "68000") (pin "11") (pinfunction "BG_11") (pintype "output"))
      (node (ref "SJ1") (pin "2") (pinfunction "2_2") (pintype "passive"))
    )
    (net (code "113") (name "BGACK") (class "Default")
      (node (ref "68000") (pin "12") (pinfunction "BGACK_12") (pintype "input"))
      (node (ref "SJ2") (pin "2") (pinfunction "2_2") (pintype "passive"))
    )
    (net (code "114") (name "BGKI") (class "Default")
      (node (ref "BLITTER") (pin "40") (pinfunction "BGKI_40") (pintype "bidirectional"))
      (node (ref "IC1") (pin "12") (pinfunction "BGACK_12") (pintype "input"))
      (node (ref "SJ2") (pin "3") (pinfunction "3_3") (pintype "passive"))
    )
    (net (code "115") (name "BGO") (class "Default")
      (node (ref "BLITTER") (pin "37") (pinfunction "BGO_37") (pintype "bidirectional"))
      (node (ref "IC1") (pin "11") (pinfunction "BG_11") (pintype "output"))
      (node (ref "SJ1") (pin "3") (pinfunction "3_3") (pintype "passive"))
    )
    (net (code "116") (name "BIRQ") (class "Default")
      (node (ref "BLITTER") (pin "41") (pinfunction "INT_41") (pintype "bidirectional"))
      (node (ref "J1") (pin "5") (pinfunction "5_5") (pintype "passive"))
    )
    (net (code "117") (name "CLK") (class "Default")
      (node (ref "68000") (pin "15") (pinfunction "CLK_15") (pintype "input"))
      (node (ref "BLITTER") (pin "34") (pinfunction "CLK_34") (pintype "bidirectional"))
      (node (ref "IC1") (pin "15") (pinfunction "CLK_15") (pintype "input"))
      (node (ref "J4") (pin "5") (pinfunction "5_5") (pintype "passive"))
      (node (ref "U1") (pin "87") (pinfunction "INPUT/GCLK1_87") (pintype "input"))
    )
    (net (code "118") (name "ET_EN") (class "Default")
      (node (ref "R9") (pin "2") (pinfunction "2_2") (pintype "passive"))
      (node (ref "SJ7") (pin "2") (pinfunction "2_2") (pintype "passive"))
      (node (ref "U1") (pin "93") (pinfunction "52_I/O_93") (pintype "bidirectional"))
    )
    (net (code "119") (name "ET_IORD") (class "Default")
      (node (ref "STGA") (pin "15") (pinfunction "/IORD_15") (pintype "bidirectional"))
      (node (ref "U1") (pin "64") (pinfunction "36_I/O_64") (pintype "bidirectional"))
    )
    (net (code "120") (name "ET_IOWR") (class "Default")
      (node (ref "STGA") (pin "14") (pinfunction "/IOWR_14") (pintype "bidirectional"))
      (node (ref "U1") (pin "67") (pinfunction "38_I/O_67") (pintype "bidirectional"))
    )
    (net (code "121") (name "ET_IRQ") (class "Default")
      (node (ref "STGA") (pin "1") (pinfunction "NC_1") (pintype "bidirectional"))
      (node (ref "U1") (pin "75") (pinfunction "42_I/O_75") (pintype "bidirectional"))
    )
    (net (code "122") (name "ET_MEMRD") (class "Default")
      (node (ref "STGA") (pin "13") (pinfunction "/MEMRD_13") (pintype "bidirectional"))
      (node (ref "U1") (pin "65") (pinfunction "37_I/O_65") (pintype "bidirectional"))
    )
    (net (code "123") (name "ET_MEMWR") (class "Default")
      (node (ref "STGA") (pin "12") (pinfunction "/MEMWR_12") (pintype "bidirectional"))
      (node (ref "U1") (pin "69") (pinfunction "40_I/O_69") (pintype "bidirectional"))
    )
    (net (code "124") (name "ET_RDY") (class "Default")
      (node (ref "STGA") (pin "11") (pinfunction "RDY_11") (pintype "bidirectional"))
      (node (ref "U1") (pin "68") (pinfunction "39_I/O_68") (pintype "bidirectional"))
    )
    (net (code "125") (name "ET_VRES") (class "Default")
      (node (ref "STGA") (pin "2") (pinfunction "VRES_2") (pintype "bidirectional"))
      (node (ref "U1") (pin "71") (pinfunction "41_I/O_71") (pintype "bidirectional"))
    )
    (net (code "126") (name "GND") (class "Default")
      (node (ref "68000") (pin "16") (pinfunction "GND_16") (pintype "power_in"))
      (node (ref "68000") (pin "53") (pinfunction "GND_53") (pintype "power_in"))
      (node (ref "BLITTER") (pin "35") (pinfunction "GND2_35") (pintype "bidirectional"))
      (node (ref "BLITTER") (pin "5") (pinfunction "GND1_5") (pintype "bidirectional"))
      (node (ref "C1") (pin "2") (pinfunction "2_2") (pintype "passive"))
      (node (ref "C10") (pin "1") (pinfunction "1_1") (pintype "passive"))
      (node (ref "C11") (pin "1") (pinfunction "1_1") (pintype "passive"))
      (node (ref "C12") (pin "1") (pinfunction "1_1") (pintype "passive"))
      (node (ref "C2") (pin "2") (pinfunction "2_2") (pintype "passive"))
      (node (ref "C3") (pin "2") (pinfunction "2_2") (pintype "passive"))
      (node (ref "C4") (pin "2") (pinfunction "2_2") (pintype "passive"))
      (node (ref "C5") (pin "1") (pinfunction "1_1") (pintype "passive"))
      (node (ref "C6") (pin "1") (pinfunction "1_1") (pintype "passive"))
      (node (ref "C7") (pin "1") (pinfunction "1_1") (pintype "passive"))
      (node (ref "C8") (pin "1") (pinfunction "1_1") (pintype "passive"))
      (node (ref "C9") (pin "1") (pinfunction "1_1") (pintype "passive"))
      (node (ref "CFCARD") (pin "19") (pinfunction "GND_19_19") (pintype "bidirectional"))
      (node (ref "CFCARD") (pin "2") (pinfunction "GND_2_2") (pintype "bidirectional"))
      (node (ref "CFCARD") (pin "22") (pinfunction "GND_22_22") (pintype "bidirectional"))
      (node (ref "CFCARD") (pin "24") (pinfunction "GND_24_24") (pintype "bidirectional"))
      (node (ref "CFCARD") (pin "26") (pinfunction "GND_26_26") (pintype "bidirectional"))
      (node (ref "CFCARD") (pin "28") (pinfunction "CSEL_28") (pintype "bidirectional"))
      (node (ref "CFCARD") (pin "30") (pinfunction "GND_30_30") (pintype "bidirectional"))
      (node (ref "CFCARD") (pin "40") (pinfunction "GND_40_40") (pintype "bidirectional"))
      (node (ref "CFCARD") (pin "43") (pinfunction "GND_43_43") (pintype "bidirectional"))
      (node (ref "CFCARD") (pin "44") (pinfunction "TYPE_44") (pintype "bidirectional"))
      (node (ref "IC1") (pin "16") (pinfunction "GND_16") (pintype "power_in"))
      (node (ref "IC1") (pin "53") (pinfunction "GND_53") (pintype "power_in"))
      (node (ref "J4") (pin "3") (pinfunction "3_3") (pintype "passive"))
      (node (ref "J4") (pin "4") (pinfunction "4_4") (pintype "passive"))
      (node (ref "JTAG") (pin "5") (pinfunction "GND1_5") (pintype "bidirectional"))
      (node (ref "PWR") (pin "1") (pinfunction "1_1") (pintype "passive"))
      (node (ref "SJ3") (pin "1") (pinfunction "1_1") (pintype "passive"))
      (node (ref "SJ4") (pin "1") (pinfunction "1_1") (pintype "passive"))
      (node (ref "SJ5") (pin "1") (pinfunction "1_1") (pintype "passive"))
      (node (ref "SJ6") (pin "1") (pinfunction "1_1") (pintype "passive"))
      (node (ref "SJ7") (pin "1") (pinfunction "1_1") (pintype "passive"))
      (node (ref "U1") (pin "11") (pinfunction "1_GND_11") (pintype "power_in"))
      (node (ref "U1") (pin "26") (pinfunction "2_GND_26") (pintype "power_in"))
      (node (ref "U1") (pin "38") (pinfunction "3_GND_38") (pintype "power_in"))
      (node (ref "U1") (pin "43") (pinfunction "4_GND_43") (pintype "power_in"))
      (node (ref "U1") (pin "59") (pinfunction "5_GND_59") (pintype "power_in"))
      (node (ref "U1") (pin "74") (pinfunction "6_GND_74") (pintype "power_in"))
      (node (ref "U1") (pin "86") (pinfunction "7_GND_86") (pintype "power_in"))
      (node (ref "U1") (pin "95") (pinfunction "8_GND_95") (pintype "power_in"))
    )
    (net (code "127") (name "IDE_ADDR0") (class "Default")
      (node (ref "R3") (pin "2") (pinfunction "2_2") (pintype "passive"))
      (node (ref "SJ3") (pin "2") (pinfunction "2_2") (pintype "passive"))
      (node (ref "U1") (pin "98") (pinfunction "56_I/O_98") (pintype "bidirectional"))
    )
    (net (code "128") (name "IDE_ADDR1") (class "Default")
      (node (ref "R4") (pin "2") (pinfunction "2_2") (pintype "passive"))
      (node (ref "SJ4") (pin "2") (pinfunction "2_2") (pintype "passive"))
      (node (ref "U1") (pin "97") (pinfunction "55_I/O_97") (pintype "bidirectional"))
    )
    (net (code "129") (name "IDE_CS0") (class "Default")
      (node (ref "CFCARD") (pin "37") (pinfunction "CS0_37") (pintype "bidirectional"))
      (node (ref "U1") (pin "100") (pinfunction "2_I/O_100") (pintype "bidirectional"))
    )
    (net (code "130") (name "IDE_CS1") (class "Default")
      (node (ref "CFCARD") (pin "38") (pinfunction "CS1_38") (pintype "bidirectional"))
      (node (ref "U1") (pin "99") (pinfunction "57_I/O_99") (pintype "bidirectional"))
    )
    (net (code "131") (name "IDE_EN") (class "Default")
      (node (ref "R7") (pin "2") (pinfunction "2_2") (pintype "passive"))
      (node (ref "SJ5") (pin "2") (pinfunction "2_2") (pintype "passive"))
      (node (ref "U1") (pin "96") (pinfunction "54_I/O_96") (pintype "bidirectional"))
    )
    (net (code "132") (name "IDE_IRQ") (class "Default")
      (node (ref "CFCARD") (pin "31") (pinfunction "IRQ_31") (pintype "bidirectional"))
      (node (ref "U1") (pin "6") (pinfunction "32_I/O_6") (pintype "bidirectional"))
    )
    (net (code "133") (name "IDE_RD") (class "Default")
      (node (ref "CFCARD") (pin "25") (pinfunction "RD_25") (pintype "bidirectional"))
      (node (ref "U1") (pin "9") (pinfunction "50_I/O_9") (pintype "bidirectional"))
    )
    (net (code "134") (name "IDE_RDY") (class "Default")
      (node (ref "CFCARD") (pin "27") (pinfunction "IORDY_27") (pintype "bidirectional"))
      (node (ref "U1") (pin "8") (pinfunction "45_I/O_8") (pintype "bidirectional"))
    )
    (net (code "135") (name "IDE_WR") (class "Default")
      (node (ref "CFCARD") (pin "23") (pinfunction "WR_23") (pintype "bidirectional"))
      (node (ref "U1") (pin "10") (pinfunction "1_I/O_10") (pintype "bidirectional"))
    )
    (net (code "136") (name "Net-(BLITTER-BGACK)") (class "Default")
      (node (ref "BLITTER") (pin "29") (pinfunction "BGACK_29") (pintype "bidirectional"))
      (node (ref "R2") (pin "1") (pinfunction "1_1") (pintype "passive"))
      (node (ref "SJ2") (pin "1") (pinfunction "1_1") (pintype "passive"))
    )
    (net (code "137") (name "Net-(BLITTER-BGI)") (class "Default")
      (node (ref "BLITTER") (pin "28") (pinfunction "BGI_28") (pintype "bidirectional"))
      (node (ref "R1") (pin "1") (pinfunction "1_1") (pintype "passive"))
      (node (ref "SJ1") (pin "1") (pinfunction "1_1") (pintype "passive"))
    )
    (net (code "138") (name "Net-(CFCARD-DASP)") (class "Default")
      (node (ref "CFCARD") (pin "39") (pinfunction "DASP_39") (pintype "bidirectional"))
      (node (ref "R5") (pin "1") (pinfunction "1_1") (pintype "passive"))
    )
    (net (code "139") (name "Net-(CFCARD-DMACK)") (class "Default")
      (node (ref "CFCARD") (pin "29") (pinfunction "DMACK_29") (pintype "bidirectional"))
      (node (ref "R6") (pin "2") (pinfunction "2_2") (pintype "passive"))
    )
    (net (code "140") (name "Net-(LED1-C)") (class "Default")
      (node (ref "LED1") (pin "K") (pinfunction "C_K") (pintype "passive"))
      (node (ref "R5") (pin "2") (pinfunction "2_2") (pintype "passive"))
    )
    (net (code "141") (name "RCEI") (class "Default")
      (node (ref "J1") (pin "6") (pinfunction "6_6") (pintype "passive"))
      (node (ref "U1") (pin "16") (pinfunction "5_I/O_16") (pintype "bidirectional"))
    )
    (net (code "142") (name "RCEO") (class "Default")
      (node (ref "J1") (pin "7") (pinfunction "7_7") (pintype "passive"))
      (node (ref "U1") (pin "14") (pinfunction "4_I/O_14") (pintype "bidirectional"))
    )
    (net (code "143") (name "ROM_EN") (class "Default")
      (node (ref "R8") (pin "2") (pinfunction "2_2") (pintype "passive"))
      (node (ref "SJ6") (pin "2") (pinfunction "2_2") (pintype "passive"))
      (node (ref "U1") (pin "94") (pinfunction "53_I/O_94") (pintype "bidirectional"))
    )
    (net (code "144") (name "TCK") (class "Default")
      (node (ref "JTAG") (pin "4") (pinfunction "TCK_4") (pintype "bidirectional"))
      (node (ref "U1") (pin "62") (pinfunction "I/O/TCK_62") (pintype "bidirectional"))
    )
    (net (code "145") (name "TDI") (class "Default")
      (node (ref "JTAG") (pin "2") (pinfunction "TDI_2") (pintype "bidirectional"))
      (node (ref "U1") (pin "4") (pinfunction "I/O/TDI_4") (pintype "bidirectional"))
    )
    (net (code "146") (name "TDO") (class "Default")
      (node (ref "JTAG") (pin "3") (pinfunction "TDO_3") (pintype "bidirectional"))
      (node (ref "U1") (pin "73") (pinfunction "I/O/TDO_73") (pintype "bidirectional"))
    )
    (net (code "147") (name "TMS") (class "Default")
      (node (ref "JTAG") (pin "1") (pinfunction "TMS_1") (pintype "bidirectional"))
      (node (ref "U1") (pin "15") (pinfunction "I/O/TMS_15") (pintype "bidirectional"))
    )
    (net (code "148") (name "unconnected-(CFCARD-DMARQ-Pad21)") (class "Default")
      (node (ref "CFCARD") (pin "21") (pinfunction "DMARQ_21") (pintype "bidirectional"))
    )
    (net (code "149") (name "unconnected-(CFCARD-PDIAG-Pad34)") (class "Default")
      (node (ref "CFCARD") (pin "34") (pinfunction "PDIAG_34") (pintype "bidirectional"))
    )
    (net (code "150") (name "unconnected-(CFCARD-Pad32)") (class "Default")
      (node (ref "CFCARD") (pin "32") (pinfunction "32_32") (pintype "bidirectional"))
    )
    (net (code "151") (name "unconnected-(U1-1_NC-Pad1)") (class "Default")
      (node (ref "U1") (pin "1") (pinfunction "1_NC_1") (pintype "passive"))
    )
    (net (code "152") (name "unconnected-(U1-2_NC-Pad2)") (class "Default")
      (node (ref "U1") (pin "2") (pinfunction "2_NC_2") (pintype "passive"))
    )
    (net (code "153") (name "unconnected-(U1-3_NC-Pad22)") (class "Default")
      (node (ref "U1") (pin "22") (pinfunction "3_NC_22") (pintype "passive"))
    )
    (net (code "154") (name "unconnected-(U1-4_NC-Pad24)") (class "Default")
      (node (ref "U1") (pin "24") (pinfunction "4_NC_24") (pintype "passive"))
    )
    (net (code "155") (name "unconnected-(U1-5_NC-Pad27)") (class "Default")
      (node (ref "U1") (pin "27") (pinfunction "5_NC_27") (pintype "passive"))
    )
    (net (code "156") (name "unconnected-(U1-6_NC-Pad28)") (class "Default")
      (node (ref "U1") (pin "28") (pinfunction "6_NC_28") (pintype "passive"))
    )
    (net (code "157") (name "unconnected-(U1-7_NC-Pad49)") (class "Default")
      (node (ref "U1") (pin "49") (pinfunction "7_NC_49") (pintype "passive"))
    )
    (net (code "158") (name "unconnected-(U1-8_NC-Pad5)") (class "Default")
      (node (ref "U1") (pin "5") (pinfunction "8_NC_5") (pintype "passive"))
    )
    (net (code "159") (name "unconnected-(U1-9_NC-Pad50)") (class "Default")
      (node (ref "U1") (pin "50") (pinfunction "9_NC_50") (pintype "passive"))
    )
    (net (code "160") (name "unconnected-(U1-10_NC-Pad53)") (class "Default")
      (node (ref "U1") (pin "53") (pinfunction "10_NC_53") (pintype "passive"))
    )
    (net (code "161") (name "unconnected-(U1-11_NC-Pad55)") (class "Default")
      (node (ref "U1") (pin "55") (pinfunction "11_NC_55") (pintype "passive"))
    )
    (net (code "162") (name "unconnected-(U1-12_NC-Pad7)") (class "Default")
      (node (ref "U1") (pin "7") (pinfunction "12_NC_7") (pintype "passive"))
    )
    (net (code "163") (name "unconnected-(U1-13_NC-Pad70)") (class "Default")
      (node (ref "U1") (pin "70") (pinfunction "13_NC_70") (pintype "passive"))
    )
    (net (code "164") (name "unconnected-(U1-14_NC-Pad72)") (class "Default")
      (node (ref "U1") (pin "72") (pinfunction "14_NC_72") (pintype "passive"))
    )
    (net (code "165") (name "unconnected-(U1-15_NC-Pad77)") (class "Default")
      (node (ref "U1") (pin "77") (pinfunction "15_NC_77") (pintype "passive"))
    )
    (net (code "166") (name "unconnected-(U1-16_NC-Pad78)") (class "Default")
      (node (ref "U1") (pin "78") (pinfunction "16_NC_78") (pintype "passive"))
    )
  )
)
